# Ham-Dip-004.net
KiCad netlist of a schematic drawn in EAGLE
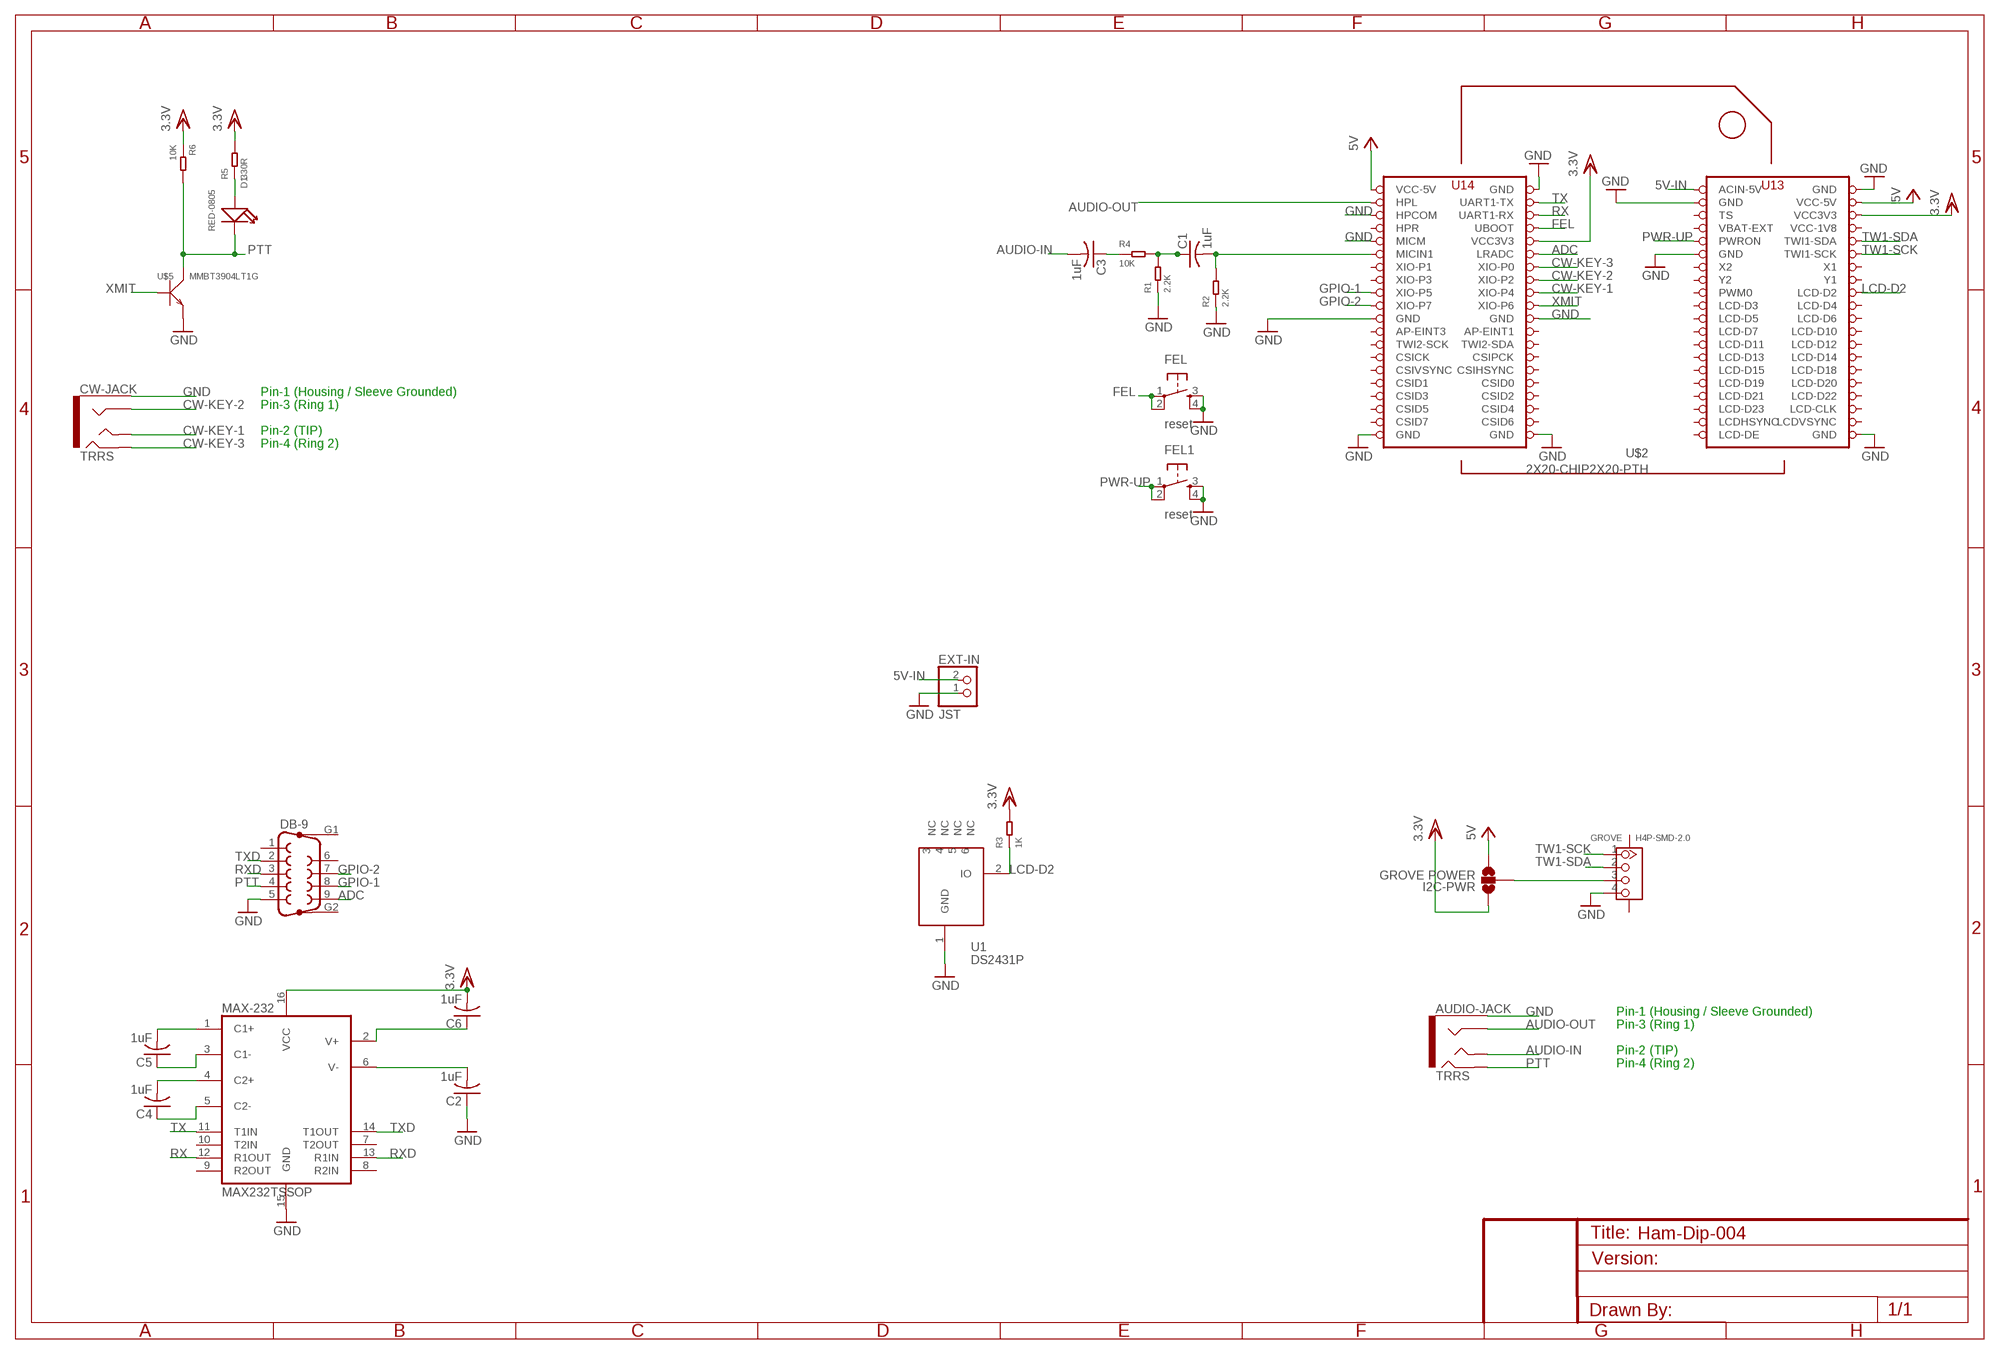
[diagram p0: schematic, sheet 1]

(export (version "E")
  (design (tool "Eeschema 10.0.6"))
  (components
    (comp (ref "AUDIO-JACK")
      (value "TRRS")
      (footprint "eagle-import:AUDIO-JACK-TRRS-SMD")
      (libsource (lib "eagle-import") (part "AUDIO-JACK3"))
    )
    (comp (ref "C1")
      (value "1uF")
      (footprint "eagle-import:C0805")
      (libsource (lib "eagle-import") (part "C-USC0805"))
    )
    (comp (ref "C2")
      (value "1uF")
      (footprint "eagle-import:C0805")
      (libsource (lib "eagle-import") (part "C-USC0805"))
    )
    (comp (ref "C3")
      (value "1uF")
      (footprint "eagle-import:C0805")
      (libsource (lib "eagle-import") (part "C-USC0805"))
    )
    (comp (ref "C4")
      (value "1uF")
      (footprint "eagle-import:C0805")
      (libsource (lib "eagle-import") (part "C-USC0805"))
    )
    (comp (ref "C5")
      (value "1uF")
      (footprint "eagle-import:C0805")
      (libsource (lib "eagle-import") (part "C-USC0805"))
    )
    (comp (ref "C6")
      (value "1uF")
      (footprint "eagle-import:C0805")
      (libsource (lib "eagle-import") (part "C-USC0805"))
    )
    (comp (ref "CW-JACK")
      (value "TRRS")
      (footprint "eagle-import:AUDIO-JACK-TRRS-SMD")
      (libsource (lib "eagle-import") (part "AUDIO-JACK3"))
    )
    (comp (ref "D1")
      (value "RED-0805")
      (footprint "eagle-import:LED-0805")
      (fields (field (name "MPN") "17-215SURC/S530-A2/TR8"))
      (libsource (lib "eagle-import") (part "SMD-LED-CLEAR-RED(0805)"))
    )
    (comp (ref "DB-9")
      (value "F09HP")
      (footprint "eagle-import:F09HP")
      (libsource (lib "eagle-import") (part "F09HP"))
    )
    (comp (ref "EXT-IN")
      (value "JST")
      (footprint "eagle-import:JST-PH-2-SMT")
      (libsource (lib "eagle-import") (part "JST_2PIN-SMT"))
    )
    (comp (ref "FEL")
      (value "reset")
      (footprint "eagle-import:TACTILE_SWITCH_SMD")
      (libsource (lib "eagle-import") (part "TAC_SWITCHSMD"))
    )
    (comp (ref "FEL1")
      (value "reset")
      (footprint "eagle-import:TACTILE_SWITCH_SMD")
      (libsource (lib "eagle-import") (part "TAC_SWITCHSMD"))
    )
    (comp (ref "GROVE")
      (value "H4P-SMD-2.0")
      (footprint "eagle-import:HW4-SMD-2.0")
      (libsource (lib "eagle-import") (part "GROVE-CONNECTOR-SMD(4+2P-2.0)"))
    )
    (comp (ref "I2C-PWR")
      (value "GROVE POWER")
      (footprint "eagle-import:SMD_SJ_3WAY_OPEN")
      (libsource (lib "eagle-import") (part "SMD_SJ_3WAY_OPENT"))
    )
    (comp (ref "MAX-232")
      (value "MAX232TSSOP")
      (footprint "eagle-import:TSSOP16")
      (libsource (lib "eagle-import") (part "MAX232TSSOP"))
    )
    (comp (ref "R1")
      (value "2.2K")
      (footprint "eagle-import:R0805")
      (fields (field (name "MPN") "RC0805JR-072K2L"))
      (libsource (lib "eagle-import") (part "SMD-RES-2.2K-5%-1/8W(0805)"))
    )
    (comp (ref "R2")
      (value "2.2K")
      (footprint "eagle-import:R0805")
      (fields (field (name "MPN") "RC0805JR-072K2L"))
      (libsource (lib "eagle-import") (part "SMD-RES-2.2K-5%-1/8W(0805)"))
    )
    (comp (ref "R3")
      (value "1K")
      (footprint "eagle-import:R0805")
      (fields (field (name "MPN") "RC0805JR-07220RL"))
      (libsource (lib "eagle-import") (part "SMD-RES-220R-5%-1/8W(0805)"))
    )
    (comp (ref "R4")
      (value "10K")
      (footprint "eagle-import:R0805")
      (fields (field (name "MPN") "RC0805FR-0710KL"))
      (libsource (lib "eagle-import") (part "SMD-RES-10K-1%-1/8W(0805)"))
    )
    (comp (ref "R5")
      (value "330R")
      (footprint "eagle-import:R0805")
      (fields (field (name "MPN") "RC0805JR-07220RL"))
      (libsource (lib "eagle-import") (part "SMD-RES-220R-5%-1/8W(0805)"))
    )
    (comp (ref "R6")
      (value "10K")
      (footprint "eagle-import:R0805")
      (fields (field (name "MPN") "RC0805FR-0710KL"))
      (libsource (lib "eagle-import") (part "SMD-RES-10K-1%-1/8W(0805)"))
    )
    (comp (ref "U$2")
      (value "2X20-CHIP2X20-PTH")
      (footprint "eagle-import:2X20CHIP-TH")
      (fields (field (name "VENDOR_PART_NUMBER") "AWHW40-G-SMD-R (single)"))
      (libsource (lib "eagle-import") (part "2X20-CHIP2X20-PTH-CHIP_A"))
    )
    (comp (ref "U$5")
      (value "MMBT3904LT1G")
      (footprint "eagle-import:SOT-23")
      (libsource (lib "eagle-import") (part "SMD-TRANSISTORS-NPN-40V-200MA-MMBT3904LT1G(SOT-23)"))
    )
    (comp (ref "U1")
      (value "DS2431P")
      (footprint "eagle-import:TSOC6")
      (fields (field (name "MFG") "DIGIKEY") (field (name "VENDOR_PART_NUMBER") "DS2431P+T&R"))
      (libsource (lib "eagle-import") (part "DS2431P"))
    )
  )
  (nets
    (net (code "1") (name "/5V-IN") (class "Default")
      (node (ref "EXT-IN") (pin "2") (pinfunction "1_2") (pintype "passive"))
      (node (ref "U$2") (pin "CHG-IN") (pinfunction "ACIN-5V_CHG-IN") (pintype "passive"))
    )
    (net (code "2") (name "/ADC") (class "Default")
      (node (ref "DB-9") (pin "9") (pinfunction "9_9") (pintype "passive"))
      (node (ref "U$2") (pin "LRADC") (pinfunction "LRADC_LRADC") (pintype "passive"))
    )
    (net (code "3") (name "/AUDIO-IN") (class "Default")
      (node (ref "AUDIO-JACK") (pin "TIP") (pinfunction "TIP_TIP") (pintype "bidirectional"))
      (node (ref "C3") (pin "2") (pinfunction "2_2") (pintype "passive"))
    )
    (net (code "4") (name "/AUDIO-OUT") (class "Default")
      (node (ref "AUDIO-JACK") (pin "RING1") (pinfunction "RING1_RING1") (pintype "bidirectional"))
      (node (ref "U$2") (pin "HPL") (pinfunction "HPL_HPL") (pintype "passive"))
    )
    (net (code "5") (name "/CW-KEY-1") (class "Default")
      (node (ref "CW-JACK") (pin "TIP") (pinfunction "TIP_TIP") (pintype "bidirectional"))
      (node (ref "U$2") (pin "XIO-P4") (pinfunction "XIO-P4_XIO-P4") (pintype "passive"))
    )
    (net (code "6") (name "/CW-KEY-2") (class "Default")
      (node (ref "CW-JACK") (pin "RING1") (pinfunction "RING1_RING1") (pintype "bidirectional"))
      (node (ref "U$2") (pin "XIO-P2") (pinfunction "XIO-P2_XIO-P2") (pintype "passive"))
    )
    (net (code "7") (name "/CW-KEY-3") (class "Default")
      (node (ref "CW-JACK") (pin "RING2") (pinfunction "RING2_RING2") (pintype "bidirectional"))
      (node (ref "U$2") (pin "XIO-P0") (pinfunction "XIO-P0_XIO-P0") (pintype "passive"))
    )
    (net (code "8") (name "/FEL") (class "Default")
      (node (ref "FEL") (pin "1") (pinfunction "1_1") (pintype "passive"))
      (node (ref "FEL") (pin "2") (pinfunction "2_2") (pintype "passive"))
      (node (ref "U$2") (pin "FEL") (pinfunction "UBOOT_FEL") (pintype "passive"))
    )
    (net (code "9") (name "/GPIO-1") (class "Default")
      (node (ref "DB-9") (pin "8") (pinfunction "8_8") (pintype "passive"))
      (node (ref "U$2") (pin "XIO-P5") (pinfunction "XIO-P5_XIO-P5") (pintype "passive"))
    )
    (net (code "10") (name "/GPIO-2") (class "Default")
      (node (ref "DB-9") (pin "7") (pinfunction "7_7") (pintype "passive"))
      (node (ref "U$2") (pin "XIO-P7") (pinfunction "XIO-P7_XIO-P7") (pintype "passive"))
    )
    (net (code "11") (name "/LCD-D2") (class "Default")
      (node (ref "R3") (pin "1") (pinfunction "1_1") (pintype "passive"))
      (node (ref "U$2") (pin "LCD-D2") (pinfunction "LCD-D2_LCD-D2") (pintype "passive"))
      (node (ref "U1") (pin "2") (pinfunction "IO_2") (pintype "bidirectional"))
    )
    (net (code "12") (name "/PTT") (class "Default")
      (node (ref "AUDIO-JACK") (pin "RING2") (pinfunction "RING2_RING2") (pintype "bidirectional"))
      (node (ref "D1") (pin "-") (pinfunction "-_-") (pintype "passive"))
      (node (ref "DB-9") (pin "4") (pinfunction "4_4") (pintype "passive"))
      (node (ref "R6") (pin "2") (pinfunction "2_2") (pintype "passive"))
      (node (ref "U$5") (pin "3") (pinfunction "C_3") (pintype "passive"))
    )
    (net (code "13") (name "/PWR-UP") (class "Default")
      (node (ref "FEL1") (pin "1") (pinfunction "1_1") (pintype "passive"))
      (node (ref "FEL1") (pin "2") (pinfunction "2_2") (pintype "passive"))
      (node (ref "U$2") (pin "PWRON") (pinfunction "PWRON_PWRON") (pintype "passive"))
    )
    (net (code "14") (name "/RX") (class "Default")
      (node (ref "MAX-232") (pin "12") (pinfunction "R1OUT_12") (pintype "output"))
      (node (ref "U$2") (pin "UART1-RX") (pinfunction "UART1-RX_UART1-RX") (pintype "passive"))
    )
    (net (code "15") (name "/RXD") (class "Default")
      (node (ref "DB-9") (pin "3") (pinfunction "3_3") (pintype "passive"))
      (node (ref "MAX-232") (pin "13") (pinfunction "R1IN_13") (pintype "input"))
    )
    (net (code "16") (name "/TW1-SCK") (class "Default")
      (node (ref "GROVE") (pin "1") (pinfunction "1_1") (pintype "bidirectional"))
      (node (ref "U$2") (pin "TWI1-SCK") (pinfunction "TWI1-SCK_TWI1-SCK") (pintype "passive"))
    )
    (net (code "17") (name "/TW1-SDA") (class "Default")
      (node (ref "GROVE") (pin "2") (pinfunction "2_2") (pintype "bidirectional"))
      (node (ref "U$2") (pin "TWI1-SDA") (pinfunction "TWI1-SDA_TWI1-SDA") (pintype "passive"))
    )
    (net (code "18") (name "/TX") (class "Default")
      (node (ref "MAX-232") (pin "11") (pinfunction "T1IN_11") (pintype "input"))
      (node (ref "U$2") (pin "UART1-TX") (pinfunction "UART1-TX_UART1-TX") (pintype "passive"))
    )
    (net (code "19") (name "/TXD") (class "Default")
      (node (ref "DB-9") (pin "2") (pinfunction "2_2") (pintype "passive"))
      (node (ref "MAX-232") (pin "14") (pinfunction "T1OUT_14") (pintype "output"))
    )
    (net (code "20") (name "/VCC-1V8") (class "Default")
      (node (ref "U$2") (pin "VCC1V8") (pinfunction "VCC-1V8_VCC1V8") (pintype "power_in"))
    )
    (net (code "21") (name "/XMIT") (class "Default")
      (node (ref "U$2") (pin "XIO-P6") (pinfunction "XIO-P6_XIO-P6") (pintype "passive"))
      (node (ref "U$5") (pin "1") (pinfunction "B_1") (pintype "passive"))
    )
    (net (code "22") (name "3.3V") (class "Default")
      (node (ref "C6") (pin "2") (pinfunction "2_2") (pintype "passive"))
      (node (ref "I2C-PWR") (pin "1") (pinfunction "1_1") (pintype "passive"))
      (node (ref "MAX-232") (pin "16") (pinfunction "VCC_16") (pintype "bidirectional"))
      (node (ref "R3") (pin "2") (pinfunction "2_2") (pintype "passive"))
      (node (ref "R5") (pin "2") (pinfunction "2_2") (pintype "passive"))
      (node (ref "R6") (pin "1") (pinfunction "1_1") (pintype "passive"))
      (node (ref "U$2") (pin "VCC3V3") (pinfunction "VCC3V3_VCC3V3") (pintype "power_in"))
      (node (ref "U$2") (pin "VCC3V3@1") (pinfunction "VCC3V3_VCC3V3@1") (pintype "power_in"))
    )
    (net (code "23") (name "5V") (class "Default")
      (node (ref "I2C-PWR") (pin "3") (pinfunction "3_3") (pintype "passive"))
      (node (ref "U$2") (pin "VCC5V@0") (pinfunction "VCC-5V_VCC5V@0") (pintype "power_in"))
      (node (ref "U$2") (pin "VCC5V@1") (pinfunction "VCC-5V_VCC5V@1") (pintype "power_in"))
    )
    (net (code "24") (name "GND") (class "Default")
      (node (ref "AUDIO-JACK") (pin "EARTH") (pinfunction "EARTH_EARTH") (pintype "bidirectional"))
      (node (ref "C2") (pin "1") (pinfunction "1_1") (pintype "passive"))
      (node (ref "CW-JACK") (pin "EARTH") (pinfunction "EARTH_EARTH") (pintype "bidirectional"))
      (node (ref "DB-9") (pin "5") (pinfunction "5_5") (pintype "passive"))
      (node (ref "EXT-IN") (pin "1") (pinfunction "2_1") (pintype "passive"))
      (node (ref "FEL") (pin "3") (pinfunction "3_3") (pintype "passive"))
      (node (ref "FEL") (pin "4") (pinfunction "4_4") (pintype "passive"))
      (node (ref "FEL1") (pin "3") (pinfunction "3_3") (pintype "passive"))
      (node (ref "FEL1") (pin "4") (pinfunction "4_4") (pintype "passive"))
      (node (ref "GROVE") (pin "4") (pinfunction "4_4") (pintype "bidirectional"))
      (node (ref "MAX-232") (pin "15") (pinfunction "GND_15") (pintype "bidirectional"))
      (node (ref "R1") (pin "1") (pinfunction "1_1") (pintype "passive"))
      (node (ref "R2") (pin "1") (pinfunction "1_1") (pintype "passive"))
      (node (ref "U$2") (pin "GND@1") (pinfunction "GND_GND@1") (pintype "power_in"))
      (node (ref "U$2") (pin "GND@10") (pinfunction "GND_GND@10") (pintype "power_in"))
      (node (ref "U$2") (pin "GND@2") (pinfunction "GND_GND@2") (pintype "power_in"))
      (node (ref "U$2") (pin "GND@3") (pinfunction "GND_GND@3") (pintype "power_in"))
      (node (ref "U$2") (pin "GND@4") (pinfunction "GND_GND@4") (pintype "power_in"))
      (node (ref "U$2") (pin "GND@5") (pinfunction "GND_GND@5") (pintype "power_in"))
      (node (ref "U$2") (pin "GND@6") (pinfunction "GND_GND@6") (pintype "power_in"))
      (node (ref "U$2") (pin "GND@7") (pinfunction "GND_GND@7") (pintype "power_in"))
      (node (ref "U$2") (pin "GND@8") (pinfunction "GND_GND@8") (pintype "power_in"))
      (node (ref "U$2") (pin "HPCOM") (pinfunction "HPCOM_HPCOM") (pintype "passive"))
      (node (ref "U$2") (pin "MICM") (pinfunction "MICM_MICM") (pintype "passive"))
      (node (ref "U$5") (pin "2") (pinfunction "E_2") (pintype "passive"))
      (node (ref "U1") (pin "1") (pinfunction "GND_1") (pintype "bidirectional"))
    )
    (net (code "25") (name "Net-(C1-Pad1)") (class "Default")
      (node (ref "C1") (pin "1") (pinfunction "1_1") (pintype "passive"))
      (node (ref "R1") (pin "2") (pinfunction "2_2") (pintype "passive"))
      (node (ref "R4") (pin "2") (pinfunction "2_2") (pintype "passive"))
    )
    (net (code "26") (name "Net-(C1-Pad2)") (class "Default")
      (node (ref "C1") (pin "2") (pinfunction "2_2") (pintype "passive"))
      (node (ref "R2") (pin "2") (pinfunction "2_2") (pintype "passive"))
      (node (ref "U$2") (pin "MICIN1") (pinfunction "MICIN1_MICIN1") (pintype "passive"))
    )
    (net (code "27") (name "Net-(C3-Pad1)") (class "Default")
      (node (ref "C3") (pin "1") (pinfunction "1_1") (pintype "passive"))
      (node (ref "R4") (pin "1") (pinfunction "1_1") (pintype "passive"))
    )
    (net (code "28") (name "Net-(D1-Pad+)") (class "Default")
      (node (ref "D1") (pin "+") (pinfunction "+_+") (pintype "passive"))
      (node (ref "R5") (pin "1") (pinfunction "1_1") (pintype "passive"))
    )
    (net (code "29") (name "Net-(GROVE-Pad3)") (class "Default")
      (node (ref "GROVE") (pin "3") (pinfunction "3_3") (pintype "bidirectional"))
      (node (ref "I2C-PWR") (pin "2") (pinfunction "2_2") (pintype "passive"))
    )
    (net (code "30") (name "Net-(MAX-232-C1+)") (class "Default")
      (node (ref "C5") (pin "2") (pinfunction "2_2") (pintype "passive"))
      (node (ref "MAX-232") (pin "1") (pinfunction "C1+_1") (pintype "bidirectional"))
    )
    (net (code "31") (name "Net-(MAX-232-C1-)") (class "Default")
      (node (ref "C5") (pin "1") (pinfunction "1_1") (pintype "passive"))
      (node (ref "MAX-232") (pin "3") (pinfunction "C1-_3") (pintype "bidirectional"))
    )
    (net (code "32") (name "Net-(MAX-232-C2+)") (class "Default")
      (node (ref "C4") (pin "2") (pinfunction "2_2") (pintype "passive"))
      (node (ref "MAX-232") (pin "4") (pinfunction "C2+_4") (pintype "bidirectional"))
    )
    (net (code "33") (name "Net-(MAX-232-C2-)") (class "Default")
      (node (ref "C4") (pin "1") (pinfunction "1_1") (pintype "passive"))
      (node (ref "MAX-232") (pin "5") (pinfunction "C2-_5") (pintype "bidirectional"))
    )
    (net (code "34") (name "Net-(MAX-232-V+)") (class "Default")
      (node (ref "C6") (pin "1") (pinfunction "1_1") (pintype "passive"))
      (node (ref "MAX-232") (pin "2") (pinfunction "V+_2") (pintype "bidirectional"))
    )
    (net (code "35") (name "Net-(MAX-232-V-)") (class "Default")
      (node (ref "C2") (pin "2") (pinfunction "2_2") (pintype "passive"))
      (node (ref "MAX-232") (pin "6") (pinfunction "V-_6") (pintype "bidirectional"))
    )
    (net (code "36") (name "unconnected-(DB-9-Pad1)") (class "Default")
      (node (ref "DB-9") (pin "1") (pinfunction "1_1") (pintype "passive"))
    )
    (net (code "37") (name "unconnected-(DB-9-Pad6)") (class "Default")
      (node (ref "DB-9") (pin "6") (pinfunction "6_6") (pintype "passive"))
    )
    (net (code "38") (name "unconnected-(DB-9-PadG1)") (class "Default")
      (node (ref "DB-9") (pin "G1") (pinfunction "G1_G1") (pintype "passive"))
    )
    (net (code "39") (name "unconnected-(DB-9-PadG2)") (class "Default")
      (node (ref "DB-9") (pin "G2") (pinfunction "G2_G2") (pintype "passive"))
    )
    (net (code "40") (name "unconnected-(GROVE-PadSS1)") (class "Default")
      (node (ref "GROVE") (pin "SS1") (pinfunction "SS1_SS1") (pintype "bidirectional"))
    )
    (net (code "41") (name "unconnected-(GROVE-PadSS2)") (class "Default")
      (node (ref "GROVE") (pin "SS2") (pinfunction "SS2_SS2") (pintype "bidirectional"))
    )
    (net (code "42") (name "unconnected-(MAX-232-R2IN-Pad8)") (class "Default")
      (node (ref "MAX-232") (pin "8") (pinfunction "R2IN_8") (pintype "input"))
    )
    (net (code "43") (name "unconnected-(MAX-232-R2OUT-Pad9)") (class "Default")
      (node (ref "MAX-232") (pin "9") (pinfunction "R2OUT_9") (pintype "output"))
    )
    (net (code "44") (name "unconnected-(MAX-232-T2IN-Pad10)") (class "Default")
      (node (ref "MAX-232") (pin "10") (pinfunction "T2IN_10") (pintype "input"))
    )
    (net (code "45") (name "unconnected-(MAX-232-T2OUT-Pad7)") (class "Default")
      (node (ref "MAX-232") (pin "7") (pinfunction "T2OUT_7") (pintype "output"))
    )
    (net (code "46") (name "unconnected-(U$2-LCDHSYNC-PadLCD-HSYNC)") (class "Default")
      (node (ref "U$2") (pin "LCD-HSYNC") (pinfunction "LCDHSYNC_LCD-HSYNC") (pintype "passive"))
    )
    (net (code "47") (name "unconnected-(U$2-LCDVSYNC-PadLCD-VSYNC)") (class "Default")
      (node (ref "U$2") (pin "LCD-VSYNC") (pinfunction "LCDVSYNC_LCD-VSYNC") (pintype "passive"))
    )
    (net (code "48") (name "unconnected-(U$2-PadAP-EINT1)") (class "Default")
      (node (ref "U$2") (pin "AP-EINT1") (pinfunction "AP-EINT1_AP-EINT1") (pintype "passive"))
    )
    (net (code "49") (name "unconnected-(U$2-PadAP-EINT3)") (class "Default")
      (node (ref "U$2") (pin "AP-EINT3") (pinfunction "AP-EINT3_AP-EINT3") (pintype "passive"))
    )
    (net (code "50") (name "unconnected-(U$2-PadCSICK)") (class "Default")
      (node (ref "U$2") (pin "CSICK") (pinfunction "CSICK_CSICK") (pintype "passive"))
    )
    (net (code "51") (name "unconnected-(U$2-PadCSID0)") (class "Default")
      (node (ref "U$2") (pin "CSID0") (pinfunction "CSID0_CSID0") (pintype "passive"))
    )
    (net (code "52") (name "unconnected-(U$2-PadCSID1)") (class "Default")
      (node (ref "U$2") (pin "CSID1") (pinfunction "CSID1_CSID1") (pintype "passive"))
    )
    (net (code "53") (name "unconnected-(U$2-PadCSID2)") (class "Default")
      (node (ref "U$2") (pin "CSID2") (pinfunction "CSID2_CSID2") (pintype "passive"))
    )
    (net (code "54") (name "unconnected-(U$2-PadCSID3)") (class "Default")
      (node (ref "U$2") (pin "CSID3") (pinfunction "CSID3_CSID3") (pintype "passive"))
    )
    (net (code "55") (name "unconnected-(U$2-PadCSID4)") (class "Default")
      (node (ref "U$2") (pin "CSID4") (pinfunction "CSID4_CSID4") (pintype "passive"))
    )
    (net (code "56") (name "unconnected-(U$2-PadCSID5)") (class "Default")
      (node (ref "U$2") (pin "CSID5") (pinfunction "CSID5_CSID5") (pintype "passive"))
    )
    (net (code "57") (name "unconnected-(U$2-PadCSID6)") (class "Default")
      (node (ref "U$2") (pin "CSID6") (pinfunction "CSID6_CSID6") (pintype "passive"))
    )
    (net (code "58") (name "unconnected-(U$2-PadCSID7)") (class "Default")
      (node (ref "U$2") (pin "CSID7") (pinfunction "CSID7_CSID7") (pintype "passive"))
    )
    (net (code "59") (name "unconnected-(U$2-PadCSIHSYNC)") (class "Default")
      (node (ref "U$2") (pin "CSIHSYNC") (pinfunction "CSIHSYNC_CSIHSYNC") (pintype "passive"))
    )
    (net (code "60") (name "unconnected-(U$2-PadCSIPCK)") (class "Default")
      (node (ref "U$2") (pin "CSIPCK") (pinfunction "CSIPCK_CSIPCK") (pintype "passive"))
    )
    (net (code "61") (name "unconnected-(U$2-PadCSIVSYNC)") (class "Default")
      (node (ref "U$2") (pin "CSIVSYNC") (pinfunction "CSIVSYNC_CSIVSYNC") (pintype "passive"))
    )
    (net (code "62") (name "unconnected-(U$2-PadHPR)") (class "Default")
      (node (ref "U$2") (pin "HPR") (pinfunction "HPR_HPR") (pintype "passive"))
    )
    (net (code "63") (name "unconnected-(U$2-PadLCD-CLK)") (class "Default")
      (node (ref "U$2") (pin "LCD-CLK") (pinfunction "LCD-CLK_LCD-CLK") (pintype "passive"))
    )
    (net (code "64") (name "unconnected-(U$2-PadLCD-D3)") (class "Default")
      (node (ref "U$2") (pin "LCD-D3") (pinfunction "LCD-D3_LCD-D3") (pintype "passive"))
    )
    (net (code "65") (name "unconnected-(U$2-PadLCD-D4)") (class "Default")
      (node (ref "U$2") (pin "LCD-D4") (pinfunction "LCD-D4_LCD-D4") (pintype "passive"))
    )
    (net (code "66") (name "unconnected-(U$2-PadLCD-D5)") (class "Default")
      (node (ref "U$2") (pin "LCD-D5") (pinfunction "LCD-D5_LCD-D5") (pintype "passive"))
    )
    (net (code "67") (name "unconnected-(U$2-PadLCD-D6)") (class "Default")
      (node (ref "U$2") (pin "LCD-D6") (pinfunction "LCD-D6_LCD-D6") (pintype "passive"))
    )
    (net (code "68") (name "unconnected-(U$2-PadLCD-D7)") (class "Default")
      (node (ref "U$2") (pin "LCD-D7") (pinfunction "LCD-D7_LCD-D7") (pintype "passive"))
    )
    (net (code "69") (name "unconnected-(U$2-PadLCD-D10)") (class "Default")
      (node (ref "U$2") (pin "LCD-D10") (pinfunction "LCD-D10_LCD-D10") (pintype "passive"))
    )
    (net (code "70") (name "unconnected-(U$2-PadLCD-D11)") (class "Default")
      (node (ref "U$2") (pin "LCD-D11") (pinfunction "LCD-D11_LCD-D11") (pintype "passive"))
    )
    (net (code "71") (name "unconnected-(U$2-PadLCD-D12)") (class "Default")
      (node (ref "U$2") (pin "LCD-D12") (pinfunction "LCD-D12_LCD-D12") (pintype "passive"))
    )
    (net (code "72") (name "unconnected-(U$2-PadLCD-D13)") (class "Default")
      (node (ref "U$2") (pin "LCD-D13") (pinfunction "LCD-D13_LCD-D13") (pintype "passive"))
    )
    (net (code "73") (name "unconnected-(U$2-PadLCD-D14)") (class "Default")
      (node (ref "U$2") (pin "LCD-D14") (pinfunction "LCD-D14_LCD-D14") (pintype "passive"))
    )
    (net (code "74") (name "unconnected-(U$2-PadLCD-D15)") (class "Default")
      (node (ref "U$2") (pin "LCD-D15") (pinfunction "LCD-D15_LCD-D15") (pintype "passive"))
    )
    (net (code "75") (name "unconnected-(U$2-PadLCD-D18)") (class "Default")
      (node (ref "U$2") (pin "LCD-D18") (pinfunction "LCD-D18_LCD-D18") (pintype "passive"))
    )
    (net (code "76") (name "unconnected-(U$2-PadLCD-D19)") (class "Default")
      (node (ref "U$2") (pin "LCD-D19") (pinfunction "LCD-D19_LCD-D19") (pintype "passive"))
    )
    (net (code "77") (name "unconnected-(U$2-PadLCD-D20)") (class "Default")
      (node (ref "U$2") (pin "LCD-D20") (pinfunction "LCD-D20_LCD-D20") (pintype "passive"))
    )
    (net (code "78") (name "unconnected-(U$2-PadLCD-D21)") (class "Default")
      (node (ref "U$2") (pin "LCD-D21") (pinfunction "LCD-D21_LCD-D21") (pintype "passive"))
    )
    (net (code "79") (name "unconnected-(U$2-PadLCD-D22)") (class "Default")
      (node (ref "U$2") (pin "LCD-D22") (pinfunction "LCD-D22_LCD-D22") (pintype "passive"))
    )
    (net (code "80") (name "unconnected-(U$2-PadLCD-D23)") (class "Default")
      (node (ref "U$2") (pin "LCD-D23") (pinfunction "LCD-D23_LCD-D23") (pintype "passive"))
    )
    (net (code "81") (name "unconnected-(U$2-PadLCD-DE)") (class "Default")
      (node (ref "U$2") (pin "LCD-DE") (pinfunction "LCD-DE_LCD-DE") (pintype "passive"))
    )
    (net (code "82") (name "unconnected-(U$2-PadPWM0)") (class "Default")
      (node (ref "U$2") (pin "PWM0") (pinfunction "PWM0_PWM0") (pintype "passive"))
    )
    (net (code "83") (name "unconnected-(U$2-PadTS)") (class "Default")
      (node (ref "U$2") (pin "TS") (pinfunction "TS_TS") (pintype "passive"))
    )
    (net (code "84") (name "unconnected-(U$2-PadTWI2-SCK)") (class "Default")
      (node (ref "U$2") (pin "TWI2-SCK") (pinfunction "TWI2-SCK_TWI2-SCK") (pintype "passive"))
    )
    (net (code "85") (name "unconnected-(U$2-PadTWI2-SDA)") (class "Default")
      (node (ref "U$2") (pin "TWI2-SDA") (pinfunction "TWI2-SDA_TWI2-SDA") (pintype "passive"))
    )
    (net (code "86") (name "unconnected-(U$2-PadX1)") (class "Default")
      (node (ref "U$2") (pin "X1") (pinfunction "X1_X1") (pintype "passive"))
    )
    (net (code "87") (name "unconnected-(U$2-PadX2)") (class "Default")
      (node (ref "U$2") (pin "X2") (pinfunction "X2_X2") (pintype "passive"))
    )
    (net (code "88") (name "unconnected-(U$2-PadXIO-P1)") (class "Default")
      (node (ref "U$2") (pin "XIO-P1") (pinfunction "XIO-P1_XIO-P1") (pintype "passive"))
    )
    (net (code "89") (name "unconnected-(U$2-PadXIO-P3)") (class "Default")
      (node (ref "U$2") (pin "XIO-P3") (pinfunction "XIO-P3_XIO-P3") (pintype "passive"))
    )
    (net (code "90") (name "unconnected-(U$2-PadY1)") (class "Default")
      (node (ref "U$2") (pin "Y1") (pinfunction "Y1_Y1") (pintype "passive"))
    )
    (net (code "91") (name "unconnected-(U$2-PadY2)") (class "Default")
      (node (ref "U$2") (pin "Y2") (pinfunction "Y2_Y2") (pintype "passive"))
    )
    (net (code "92") (name "unconnected-(U$2-VBAT-EXT-PadBAT)") (class "Default")
      (node (ref "U$2") (pin "BAT") (pinfunction "VBAT-EXT_BAT") (pintype "passive"))
    )
    (net (code "93") (name "unconnected-(U1-NC-Pad3)") (class "Default")
      (node (ref "U1") (pin "3") (pinfunction "NC_3") (pintype "bidirectional"))
    )
    (net (code "94") (name "unconnected-(U1-NC-Pad4)") (class "Default")
      (node (ref "U1") (pin "4") (pinfunction "NC_4") (pintype "bidirectional"))
    )
    (net (code "95") (name "unconnected-(U1-NC-Pad5)") (class "Default")
      (node (ref "U1") (pin "5") (pinfunction "NC_5") (pintype "bidirectional"))
    )
    (net (code "96") (name "unconnected-(U1-NC-Pad6)") (class "Default")
      (node (ref "U1") (pin "6") (pinfunction "NC_6") (pintype "bidirectional"))
    )
  )
)
